# Spartan2Bone.net
KiCad netlist of a schematic drawn in EAGLE
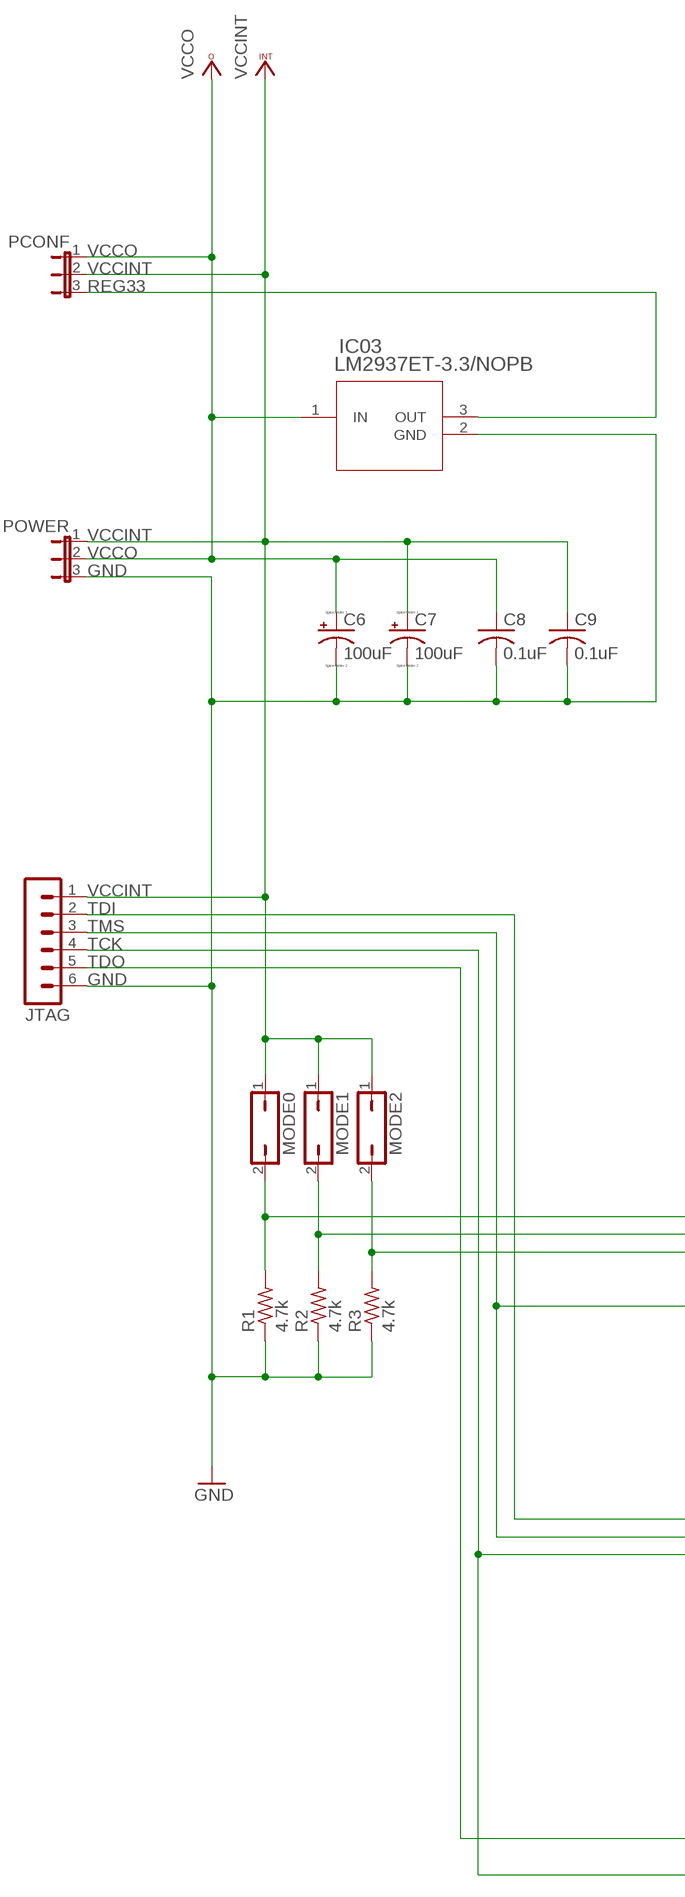
[diagram p0: schematic, sheet 1, part 1 of 2]
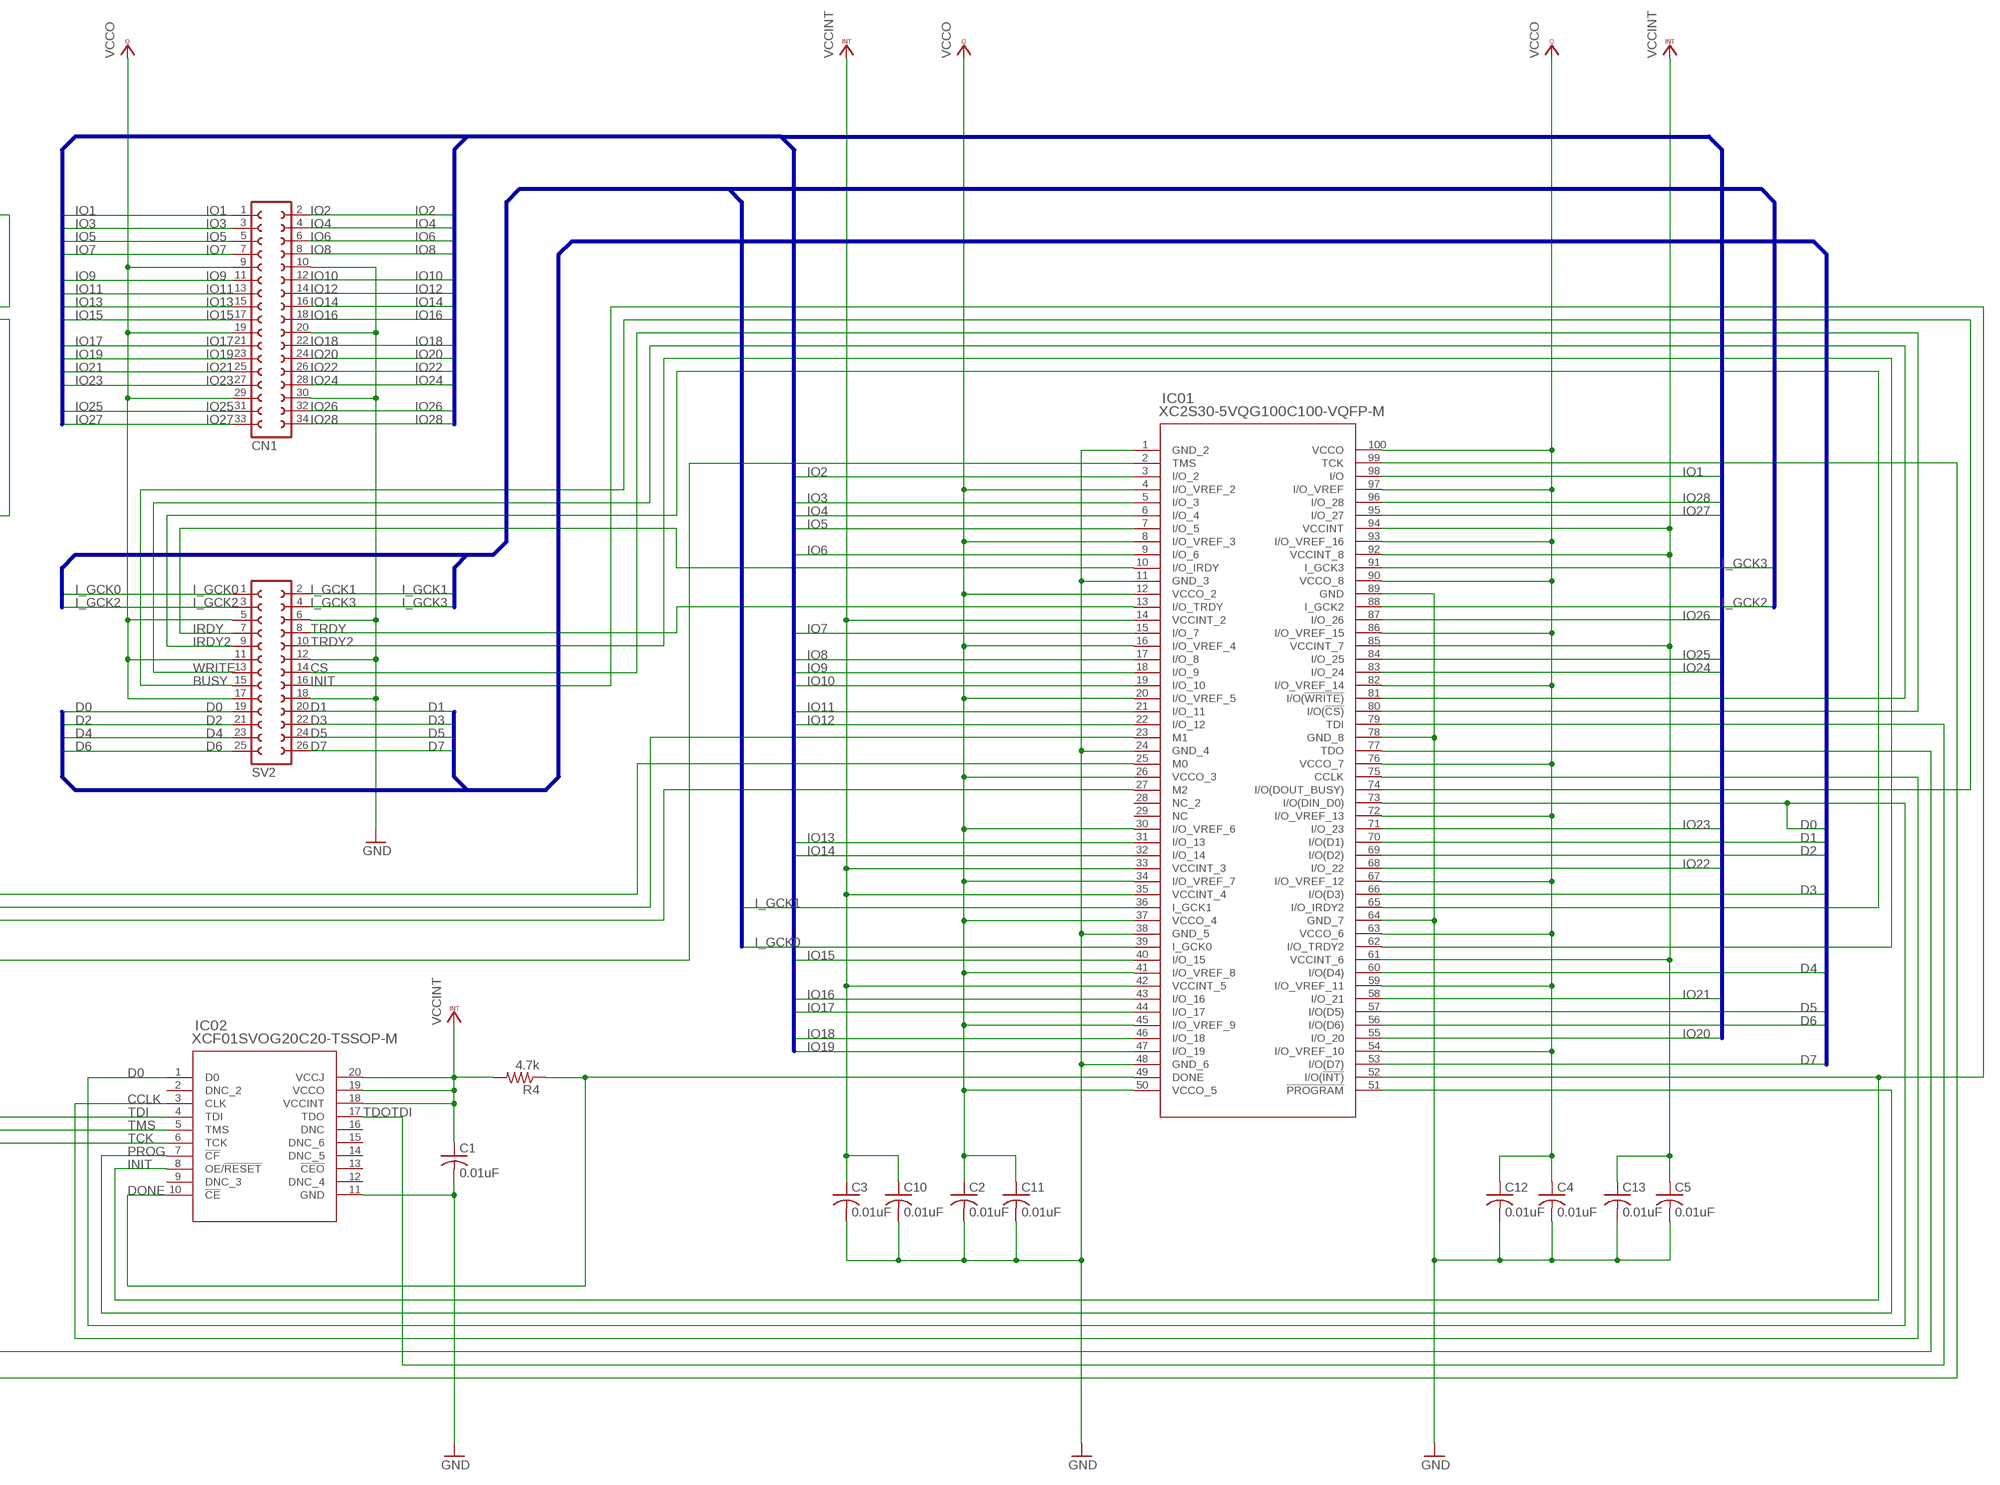
[diagram p1: schematic, sheet 1, part 2 of 2]

(export (version "E")
  (design (tool "Eeschema 10.0.6"))
  (components
    (comp (ref "C1")
      (value "0.01uF")
      (footprint "eagle-import:C050-024X044")
      (libsource (lib "eagle-import") (part "C-US050-024X044"))
    )
    (comp (ref "C2")
      (value "0.01uF")
      (footprint "eagle-import:C050-024X044")
      (libsource (lib "eagle-import") (part "C-US050-024X044"))
    )
    (comp (ref "C3")
      (value "0.01uF")
      (footprint "eagle-import:C050-024X044")
      (libsource (lib "eagle-import") (part "C-US050-024X044"))
    )
    (comp (ref "C4")
      (value "0.01uF")
      (footprint "eagle-import:C050-024X044")
      (libsource (lib "eagle-import") (part "C-US050-024X044"))
    )
    (comp (ref "C5")
      (value "0.01uF")
      (footprint "eagle-import:C050-024X044")
      (libsource (lib "eagle-import") (part "C-US050-024X044"))
    )
    (comp (ref "C6")
      (value "100uF")
      (footprint "eagle-import:E2,5-5")
      (libsource (lib "eagle-import") (part "CPOL-USE2.5-5"))
    )
    (comp (ref "C7")
      (value "100uF")
      (footprint "eagle-import:E2,5-5")
      (libsource (lib "eagle-import") (part "CPOL-USE2.5-5"))
    )
    (comp (ref "C8")
      (value "0.1uF")
      (footprint "eagle-import:C050-024X044")
      (libsource (lib "eagle-import") (part "C-US050-024X044"))
    )
    (comp (ref "C9")
      (value "0.1uF")
      (footprint "eagle-import:C050-024X044")
      (libsource (lib "eagle-import") (part "C-US050-024X044"))
    )
    (comp (ref "C10")
      (value "0.01uF")
      (footprint "eagle-import:C050-024X044")
      (libsource (lib "eagle-import") (part "C-US050-024X044"))
    )
    (comp (ref "C11")
      (value "0.01uF")
      (footprint "eagle-import:C050-024X044")
      (libsource (lib "eagle-import") (part "C-US050-024X044"))
    )
    (comp (ref "C12")
      (value "0.01uF")
      (footprint "eagle-import:C050-024X044")
      (libsource (lib "eagle-import") (part "C-US050-024X044"))
    )
    (comp (ref "C13")
      (value "0.01uF")
      (footprint "eagle-import:C050-024X044")
      (libsource (lib "eagle-import") (part "C-US050-024X044"))
    )
    (comp (ref "CN1")
      (value "FE17-2")
      (footprint "eagle-import:FE17-2")
      (libsource (lib "eagle-import") (part "FE17-2"))
    )
    (comp (ref "IC01")
      (value "XC2S30-5VQG100C100-VQFP-M")
      (footprint "eagle-import:100-VQFP-M")
      (fields (field (name "MANUFACTURER_PART_NUMBER") "XC2S305VQG100C"))
      (libsource (lib "eagle-import") (part "XC2S30-5VQG100C100-VQFP-M"))
    )
    (comp (ref "IC02")
      (value "XCF01SVOG20C20-TSSOP-M")
      (footprint "eagle-import:20-TSSOP-M")
      (fields (field (name "MANUFACTURER_PART_NUMBER") "XCF01SVOG20C"))
      (libsource (lib "eagle-import") (part "XCF01SVOG20C20-TSSOP-M"))
    )
    (comp (ref "IC03")
      (value "LM2937ET-3.3/NOPB")
      (footprint "eagle-import:T03B")
      (fields (field (name "MANUFACTURER_PART_NUMBER") "lm2937et3_3nopb"))
      (libsource (lib "eagle-import") (part "LM2937ET-3.3/NOPB"))
    )
    (comp (ref "JTAG")
      (value "MA06-1")
      (footprint "eagle-import:MA06-1")
      (libsource (lib "eagle-import") (part "MA06-1"))
    )
    (comp (ref "MODE0")
      (value "JP1Q")
      (footprint "eagle-import:JP1")
      (libsource (lib "eagle-import") (part "JP1Q"))
    )
    (comp (ref "MODE1")
      (value "JP1Q")
      (footprint "eagle-import:JP1")
      (libsource (lib "eagle-import") (part "JP1Q"))
    )
    (comp (ref "MODE2")
      (value "JP1Q")
      (footprint "eagle-import:JP1")
      (libsource (lib "eagle-import") (part "JP1Q"))
    )
    (comp (ref "PCONF")
      (value "JP2E")
      (footprint "eagle-import:JP2")
      (libsource (lib "eagle-import") (part "JP2E"))
    )
    (comp (ref "POWER")
      (value "JP2E")
      (footprint "eagle-import:JP2")
      (libsource (lib "eagle-import") (part "JP2E"))
    )
    (comp (ref "R1")
      (value "4.7k")
      (footprint "eagle-import:0204_5")
      (libsource (lib "eagle-import") (part "R-US_0204/5"))
    )
    (comp (ref "R2")
      (value "4.7k")
      (footprint "eagle-import:0204_5")
      (libsource (lib "eagle-import") (part "R-US_0204/5"))
    )
    (comp (ref "R3")
      (value "4.7k")
      (footprint "eagle-import:0204_5")
      (libsource (lib "eagle-import") (part "R-US_0204/5"))
    )
    (comp (ref "R4")
      (value "4.7k")
      (footprint "eagle-import:0204_5")
      (libsource (lib "eagle-import") (part "R-US_0204/5"))
    )
    (comp (ref "SV2")
      (value "FE13-2")
      (footprint "eagle-import:FE13-2")
      (libsource (lib "eagle-import") (part "FE13-2"))
    )
  )
  (nets
    (net (code "1") (name "/BUSY") (class "Default")
      (node (ref "IC01") (pin "74") (pinfunction "I/O(DOUT_BUSY)_74") (pintype "passive"))
      (node (ref "SV2") (pin "15") (pinfunction "15_15") (pintype "passive"))
    )
    (net (code "2") (name "/CCLK") (class "Default")
      (node (ref "IC01") (pin "75") (pinfunction "CCLK_75") (pintype "passive"))
      (node (ref "IC02") (pin "3") (pinfunction "CLK_3") (pintype "passive"))
    )
    (net (code "3") (name "/CS") (class "Default")
      (node (ref "IC01") (pin "80") (pinfunction "I/O(~{CS})_80") (pintype "passive"))
      (node (ref "SV2") (pin "14") (pinfunction "14_14") (pintype "passive"))
    )
    (net (code "4") (name "/D0") (class "Default")
      (node (ref "IC01") (pin "73") (pinfunction "I/O(DIN_D0)_73") (pintype "passive"))
      (node (ref "IC02") (pin "1") (pinfunction "D0_1") (pintype "passive"))
      (node (ref "SV2") (pin "19") (pinfunction "19_19") (pintype "passive"))
    )
    (net (code "5") (name "/D1") (class "Default")
      (node (ref "IC01") (pin "70") (pinfunction "I/O(D1)_70") (pintype "passive"))
      (node (ref "SV2") (pin "20") (pinfunction "20_20") (pintype "passive"))
    )
    (net (code "6") (name "/D2") (class "Default")
      (node (ref "IC01") (pin "69") (pinfunction "I/O(D2)_69") (pintype "passive"))
      (node (ref "SV2") (pin "21") (pinfunction "21_21") (pintype "passive"))
    )
    (net (code "7") (name "/D3") (class "Default")
      (node (ref "IC01") (pin "66") (pinfunction "I/O(D3)_66") (pintype "passive"))
      (node (ref "SV2") (pin "22") (pinfunction "22_22") (pintype "passive"))
    )
    (net (code "8") (name "/D4") (class "Default")
      (node (ref "IC01") (pin "60") (pinfunction "I/O(D4)_60") (pintype "passive"))
      (node (ref "SV2") (pin "23") (pinfunction "23_23") (pintype "passive"))
    )
    (net (code "9") (name "/D5") (class "Default")
      (node (ref "IC01") (pin "57") (pinfunction "I/O(D5)_57") (pintype "passive"))
      (node (ref "SV2") (pin "24") (pinfunction "24_24") (pintype "passive"))
    )
    (net (code "10") (name "/D6") (class "Default")
      (node (ref "IC01") (pin "56") (pinfunction "I/O(D6)_56") (pintype "passive"))
      (node (ref "SV2") (pin "25") (pinfunction "25_25") (pintype "passive"))
    )
    (net (code "11") (name "/D7") (class "Default")
      (node (ref "IC01") (pin "53") (pinfunction "I/O(D7)_53") (pintype "passive"))
      (node (ref "SV2") (pin "26") (pinfunction "26_26") (pintype "passive"))
    )
    (net (code "12") (name "/DONE") (class "Default")
      (node (ref "IC01") (pin "49") (pinfunction "DONE_49") (pintype "passive"))
      (node (ref "IC02") (pin "10") (pinfunction "~{CE}_10") (pintype "passive"))
      (node (ref "R4") (pin "1") (pinfunction "1_1") (pintype "passive"))
    )
    (net (code "13") (name "/INIT") (class "Default")
      (node (ref "IC01") (pin "52") (pinfunction "I/O(~{INT})_52") (pintype "passive"))
      (node (ref "IC02") (pin "8") (pinfunction "OE/~{RESET}_8") (pintype "passive"))
      (node (ref "SV2") (pin "16") (pinfunction "16_16") (pintype "passive"))
    )
    (net (code "14") (name "/IO1") (class "Default")
      (node (ref "CN1") (pin "1") (pinfunction "1_1") (pintype "passive"))
      (node (ref "IC01") (pin "98") (pinfunction "I/O_98") (pintype "passive"))
    )
    (net (code "15") (name "/IO2") (class "Default")
      (node (ref "CN1") (pin "2") (pinfunction "2_2") (pintype "passive"))
      (node (ref "IC01") (pin "3") (pinfunction "I/O_2_3") (pintype "passive"))
    )
    (net (code "16") (name "/IO3") (class "Default")
      (node (ref "CN1") (pin "3") (pinfunction "3_3") (pintype "passive"))
      (node (ref "IC01") (pin "5") (pinfunction "I/O_3_5") (pintype "passive"))
    )
    (net (code "17") (name "/IO4") (class "Default")
      (node (ref "CN1") (pin "4") (pinfunction "4_4") (pintype "passive"))
      (node (ref "IC01") (pin "6") (pinfunction "I/O_4_6") (pintype "passive"))
    )
    (net (code "18") (name "/IO5") (class "Default")
      (node (ref "CN1") (pin "5") (pinfunction "5_5") (pintype "passive"))
      (node (ref "IC01") (pin "7") (pinfunction "I/O_5_7") (pintype "passive"))
    )
    (net (code "19") (name "/IO6") (class "Default")
      (node (ref "CN1") (pin "6") (pinfunction "6_6") (pintype "passive"))
      (node (ref "IC01") (pin "9") (pinfunction "I/O_6_9") (pintype "passive"))
    )
    (net (code "20") (name "/IO7") (class "Default")
      (node (ref "CN1") (pin "7") (pinfunction "7_7") (pintype "passive"))
      (node (ref "IC01") (pin "15") (pinfunction "I/O_7_15") (pintype "passive"))
    )
    (net (code "21") (name "/IO8") (class "Default")
      (node (ref "CN1") (pin "8") (pinfunction "8_8") (pintype "passive"))
      (node (ref "IC01") (pin "17") (pinfunction "I/O_8_17") (pintype "passive"))
    )
    (net (code "22") (name "/IO9") (class "Default")
      (node (ref "CN1") (pin "11") (pinfunction "11_11") (pintype "passive"))
      (node (ref "IC01") (pin "18") (pinfunction "I/O_9_18") (pintype "passive"))
    )
    (net (code "23") (name "/IO10") (class "Default")
      (node (ref "CN1") (pin "12") (pinfunction "12_12") (pintype "passive"))
      (node (ref "IC01") (pin "19") (pinfunction "I/O_10_19") (pintype "passive"))
    )
    (net (code "24") (name "/IO11") (class "Default")
      (node (ref "CN1") (pin "13") (pinfunction "13_13") (pintype "passive"))
      (node (ref "IC01") (pin "21") (pinfunction "I/O_11_21") (pintype "passive"))
    )
    (net (code "25") (name "/IO12") (class "Default")
      (node (ref "CN1") (pin "14") (pinfunction "14_14") (pintype "passive"))
      (node (ref "IC01") (pin "22") (pinfunction "I/O_12_22") (pintype "passive"))
    )
    (net (code "26") (name "/IO13") (class "Default")
      (node (ref "CN1") (pin "15") (pinfunction "15_15") (pintype "passive"))
      (node (ref "IC01") (pin "31") (pinfunction "I/O_13_31") (pintype "passive"))
    )
    (net (code "27") (name "/IO14") (class "Default")
      (node (ref "CN1") (pin "16") (pinfunction "16_16") (pintype "passive"))
      (node (ref "IC01") (pin "32") (pinfunction "I/O_14_32") (pintype "passive"))
    )
    (net (code "28") (name "/IO15") (class "Default")
      (node (ref "CN1") (pin "17") (pinfunction "17_17") (pintype "passive"))
      (node (ref "IC01") (pin "40") (pinfunction "I/O_15_40") (pintype "passive"))
    )
    (net (code "29") (name "/IO16") (class "Default")
      (node (ref "CN1") (pin "18") (pinfunction "18_18") (pintype "passive"))
      (node (ref "IC01") (pin "43") (pinfunction "I/O_16_43") (pintype "passive"))
    )
    (net (code "30") (name "/IO17") (class "Default")
      (node (ref "CN1") (pin "21") (pinfunction "21_21") (pintype "passive"))
      (node (ref "IC01") (pin "44") (pinfunction "I/O_17_44") (pintype "passive"))
    )
    (net (code "31") (name "/IO18") (class "Default")
      (node (ref "CN1") (pin "22") (pinfunction "22_22") (pintype "passive"))
      (node (ref "IC01") (pin "46") (pinfunction "I/O_18_46") (pintype "passive"))
    )
    (net (code "32") (name "/IO19") (class "Default")
      (node (ref "CN1") (pin "23") (pinfunction "23_23") (pintype "passive"))
      (node (ref "IC01") (pin "47") (pinfunction "I/O_19_47") (pintype "passive"))
    )
    (net (code "33") (name "/IO20") (class "Default")
      (node (ref "CN1") (pin "24") (pinfunction "24_24") (pintype "passive"))
      (node (ref "IC01") (pin "55") (pinfunction "I/O_20_55") (pintype "passive"))
    )
    (net (code "34") (name "/IO21") (class "Default")
      (node (ref "CN1") (pin "25") (pinfunction "25_25") (pintype "passive"))
      (node (ref "IC01") (pin "58") (pinfunction "I/O_21_58") (pintype "passive"))
    )
    (net (code "35") (name "/IO22") (class "Default")
      (node (ref "CN1") (pin "26") (pinfunction "26_26") (pintype "passive"))
      (node (ref "IC01") (pin "68") (pinfunction "I/O_22_68") (pintype "passive"))
    )
    (net (code "36") (name "/IO23") (class "Default")
      (node (ref "CN1") (pin "27") (pinfunction "27_27") (pintype "passive"))
      (node (ref "IC01") (pin "71") (pinfunction "I/O_23_71") (pintype "passive"))
    )
    (net (code "37") (name "/IO24") (class "Default")
      (node (ref "CN1") (pin "28") (pinfunction "28_28") (pintype "passive"))
      (node (ref "IC01") (pin "83") (pinfunction "I/O_24_83") (pintype "passive"))
    )
    (net (code "38") (name "/IO25") (class "Default")
      (node (ref "CN1") (pin "31") (pinfunction "31_31") (pintype "passive"))
      (node (ref "IC01") (pin "84") (pinfunction "I/O_25_84") (pintype "passive"))
    )
    (net (code "39") (name "/IO26") (class "Default")
      (node (ref "CN1") (pin "32") (pinfunction "32_32") (pintype "passive"))
      (node (ref "IC01") (pin "87") (pinfunction "I/O_26_87") (pintype "passive"))
    )
    (net (code "40") (name "/IO27") (class "Default")
      (node (ref "CN1") (pin "33") (pinfunction "33_33") (pintype "passive"))
      (node (ref "IC01") (pin "95") (pinfunction "I/O_27_95") (pintype "passive"))
    )
    (net (code "41") (name "/IO28") (class "Default")
      (node (ref "CN1") (pin "34") (pinfunction "34_34") (pintype "passive"))
      (node (ref "IC01") (pin "96") (pinfunction "I/O_28_96") (pintype "passive"))
    )
    (net (code "42") (name "/IRDY") (class "Default")
      (node (ref "IC01") (pin "10") (pinfunction "I/O_IRDY_10") (pintype "passive"))
      (node (ref "SV2") (pin "7") (pinfunction "7_7") (pintype "passive"))
    )
    (net (code "43") (name "/IRDY2") (class "Default")
      (node (ref "IC01") (pin "65") (pinfunction "I/O_IRDY2_65") (pintype "passive"))
      (node (ref "SV2") (pin "9") (pinfunction "9_9") (pintype "passive"))
    )
    (net (code "44") (name "/I_GCK0") (class "Default")
      (node (ref "IC01") (pin "39") (pinfunction "I_GCK0_39") (pintype "passive"))
      (node (ref "SV2") (pin "1") (pinfunction "1_1") (pintype "passive"))
    )
    (net (code "45") (name "/I_GCK1") (class "Default")
      (node (ref "IC01") (pin "36") (pinfunction "I_GCK1_36") (pintype "passive"))
      (node (ref "SV2") (pin "2") (pinfunction "2_2") (pintype "passive"))
    )
    (net (code "46") (name "/I_GCK2") (class "Default")
      (node (ref "IC01") (pin "88") (pinfunction "I_GCK2_88") (pintype "passive"))
      (node (ref "SV2") (pin "3") (pinfunction "3_3") (pintype "passive"))
    )
    (net (code "47") (name "/I_GCK3") (class "Default")
      (node (ref "IC01") (pin "91") (pinfunction "I_GCK3_91") (pintype "passive"))
      (node (ref "SV2") (pin "4") (pinfunction "4_4") (pintype "passive"))
    )
    (net (code "48") (name "/PROG") (class "Default")
      (node (ref "IC01") (pin "51") (pinfunction "~{PROGRAM}_51") (pintype "passive"))
      (node (ref "IC02") (pin "7") (pinfunction "~{CF}_7") (pintype "passive"))
    )
    (net (code "49") (name "/REG33") (class "Default")
      (node (ref "IC03") (pin "3") (pinfunction "OUT_3") (pintype "power_in"))
      (node (ref "PCONF") (pin "3") (pinfunction "3_3") (pintype "passive"))
    )
    (net (code "50") (name "/TCK") (class "Default")
      (node (ref "IC01") (pin "99") (pinfunction "TCK_99") (pintype "passive"))
      (node (ref "IC02") (pin "6") (pinfunction "TCK_6") (pintype "passive"))
      (node (ref "JTAG") (pin "4") (pinfunction "4_4") (pintype "passive"))
    )
    (net (code "51") (name "/TDI") (class "Default")
      (node (ref "IC02") (pin "4") (pinfunction "TDI_4") (pintype "passive"))
      (node (ref "JTAG") (pin "2") (pinfunction "2_2") (pintype "passive"))
    )
    (net (code "52") (name "/TDO") (class "Default")
      (node (ref "IC01") (pin "77") (pinfunction "TDO_77") (pintype "passive"))
      (node (ref "JTAG") (pin "5") (pinfunction "5_5") (pintype "passive"))
    )
    (net (code "53") (name "/TDOTDI") (class "Default")
      (node (ref "IC01") (pin "79") (pinfunction "TDI_79") (pintype "passive"))
      (node (ref "IC02") (pin "17") (pinfunction "TDO_17") (pintype "passive"))
    )
    (net (code "54") (name "/TMS") (class "Default")
      (node (ref "IC01") (pin "2") (pinfunction "TMS_2") (pintype "passive"))
      (node (ref "IC02") (pin "5") (pinfunction "TMS_5") (pintype "passive"))
      (node (ref "JTAG") (pin "3") (pinfunction "3_3") (pintype "passive"))
    )
    (net (code "55") (name "/TRDY") (class "Default")
      (node (ref "IC01") (pin "13") (pinfunction "I/O_TRDY_13") (pintype "passive"))
      (node (ref "SV2") (pin "8") (pinfunction "8_8") (pintype "passive"))
    )
    (net (code "56") (name "/TRDY2") (class "Default")
      (node (ref "IC01") (pin "62") (pinfunction "I/O_TRDY2_62") (pintype "passive"))
      (node (ref "SV2") (pin "10") (pinfunction "10_10") (pintype "passive"))
    )
    (net (code "57") (name "/WRITE") (class "Default")
      (node (ref "IC01") (pin "81") (pinfunction "I/O(~{WRITE})_81") (pintype "passive"))
      (node (ref "SV2") (pin "13") (pinfunction "13_13") (pintype "passive"))
    )
    (net (code "58") (name "GND") (class "Default")
      (node (ref "C1") (pin "2") (pinfunction "2_2") (pintype "passive"))
      (node (ref "C10") (pin "2") (pinfunction "2_2") (pintype "passive"))
      (node (ref "C11") (pin "2") (pinfunction "2_2") (pintype "passive"))
      (node (ref "C12") (pin "2") (pinfunction "2_2") (pintype "passive"))
      (node (ref "C13") (pin "2") (pinfunction "2_2") (pintype "passive"))
      (node (ref "C2") (pin "2") (pinfunction "2_2") (pintype "passive"))
      (node (ref "C3") (pin "2") (pinfunction "2_2") (pintype "passive"))
      (node (ref "C4") (pin "2") (pinfunction "2_2") (pintype "passive"))
      (node (ref "C5") (pin "2") (pinfunction "2_2") (pintype "passive"))
      (node (ref "C6") (pin "-") (pinfunction "-_-") (pintype "passive"))
      (node (ref "C7") (pin "-") (pinfunction "-_-") (pintype "passive"))
      (node (ref "C8") (pin "2") (pinfunction "2_2") (pintype "passive"))
      (node (ref "C9") (pin "2") (pinfunction "2_2") (pintype "passive"))
      (node (ref "CN1") (pin "10") (pinfunction "10_10") (pintype "passive"))
      (node (ref "CN1") (pin "20") (pinfunction "20_20") (pintype "passive"))
      (node (ref "CN1") (pin "30") (pinfunction "30_30") (pintype "passive"))
      (node (ref "IC01") (pin "1") (pinfunction "GND_2_1") (pintype "passive"))
      (node (ref "IC01") (pin "11") (pinfunction "GND_3_11") (pintype "passive"))
      (node (ref "IC01") (pin "24") (pinfunction "GND_4_24") (pintype "passive"))
      (node (ref "IC01") (pin "38") (pinfunction "GND_5_38") (pintype "passive"))
      (node (ref "IC01") (pin "48") (pinfunction "GND_6_48") (pintype "passive"))
      (node (ref "IC01") (pin "64") (pinfunction "GND_7_64") (pintype "passive"))
      (node (ref "IC01") (pin "78") (pinfunction "GND_8_78") (pintype "passive"))
      (node (ref "IC01") (pin "89") (pinfunction "GND_89") (pintype "passive"))
      (node (ref "IC02") (pin "11") (pinfunction "GND_11") (pintype "passive"))
      (node (ref "IC03") (pin "2") (pinfunction "GND_2") (pintype "power_in"))
      (node (ref "JTAG") (pin "6") (pinfunction "6_6") (pintype "passive"))
      (node (ref "POWER") (pin "3") (pinfunction "3_3") (pintype "passive"))
      (node (ref "R1") (pin "1") (pinfunction "1_1") (pintype "passive"))
      (node (ref "R2") (pin "1") (pinfunction "1_1") (pintype "passive"))
      (node (ref "R3") (pin "1") (pinfunction "1_1") (pintype "passive"))
      (node (ref "SV2") (pin "12") (pinfunction "12_12") (pintype "passive"))
      (node (ref "SV2") (pin "18") (pinfunction "18_18") (pintype "passive"))
      (node (ref "SV2") (pin "6") (pinfunction "6_6") (pintype "passive"))
    )
    (net (code "59") (name "Net-(IC01-M0)") (class "Default")
      (node (ref "IC01") (pin "25") (pinfunction "M0_25") (pintype "passive"))
      (node (ref "MODE0") (pin "2") (pinfunction "2_2") (pintype "passive"))
      (node (ref "R1") (pin "2") (pinfunction "2_2") (pintype "passive"))
    )
    (net (code "60") (name "Net-(IC01-M1)") (class "Default")
      (node (ref "IC01") (pin "23") (pinfunction "M1_23") (pintype "passive"))
      (node (ref "MODE1") (pin "2") (pinfunction "2_2") (pintype "passive"))
      (node (ref "R2") (pin "2") (pinfunction "2_2") (pintype "passive"))
    )
    (net (code "61") (name "Net-(IC01-M2)") (class "Default")
      (node (ref "IC01") (pin "27") (pinfunction "M2_27") (pintype "passive"))
      (node (ref "MODE2") (pin "2") (pinfunction "2_2") (pintype "passive"))
      (node (ref "R3") (pin "2") (pinfunction "2_2") (pintype "passive"))
    )
    (net (code "62") (name "VCCINT") (class "Default")
      (node (ref "C1") (pin "1") (pinfunction "1_1") (pintype "passive"))
      (node (ref "C10") (pin "1") (pinfunction "1_1") (pintype "passive"))
      (node (ref "C13") (pin "1") (pinfunction "1_1") (pintype "passive"))
      (node (ref "C3") (pin "1") (pinfunction "1_1") (pintype "passive"))
      (node (ref "C5") (pin "1") (pinfunction "1_1") (pintype "passive"))
      (node (ref "C7") (pin "+") (pinfunction "+_+") (pintype "passive"))
      (node (ref "C9") (pin "1") (pinfunction "1_1") (pintype "passive"))
      (node (ref "IC01") (pin "14") (pinfunction "VCCINT_2_14") (pintype "passive"))
      (node (ref "IC01") (pin "33") (pinfunction "VCCINT_3_33") (pintype "passive"))
      (node (ref "IC01") (pin "35") (pinfunction "VCCINT_4_35") (pintype "passive"))
      (node (ref "IC01") (pin "42") (pinfunction "VCCINT_5_42") (pintype "passive"))
      (node (ref "IC01") (pin "61") (pinfunction "VCCINT_6_61") (pintype "passive"))
      (node (ref "IC01") (pin "85") (pinfunction "VCCINT_7_85") (pintype "passive"))
      (node (ref "IC01") (pin "92") (pinfunction "VCCINT_8_92") (pintype "passive"))
      (node (ref "IC01") (pin "94") (pinfunction "VCCINT_94") (pintype "passive"))
      (node (ref "IC02") (pin "18") (pinfunction "VCCINT_18") (pintype "passive"))
      (node (ref "IC02") (pin "19") (pinfunction "VCCO_19") (pintype "passive"))
      (node (ref "IC02") (pin "20") (pinfunction "VCCJ_20") (pintype "passive"))
      (node (ref "JTAG") (pin "1") (pinfunction "1_1") (pintype "passive"))
      (node (ref "MODE0") (pin "1") (pinfunction "1_1") (pintype "passive"))
      (node (ref "MODE1") (pin "1") (pinfunction "1_1") (pintype "passive"))
      (node (ref "MODE2") (pin "1") (pinfunction "1_1") (pintype "passive"))
      (node (ref "PCONF") (pin "2") (pinfunction "2_2") (pintype "passive"))
      (node (ref "POWER") (pin "1") (pinfunction "1_1") (pintype "passive"))
      (node (ref "R4") (pin "2") (pinfunction "2_2") (pintype "passive"))
    )
    (net (code "63") (name "VCCO") (class "Default")
      (node (ref "C11") (pin "1") (pinfunction "1_1") (pintype "passive"))
      (node (ref "C12") (pin "1") (pinfunction "1_1") (pintype "passive"))
      (node (ref "C2") (pin "1") (pinfunction "1_1") (pintype "passive"))
      (node (ref "C4") (pin "1") (pinfunction "1_1") (pintype "passive"))
      (node (ref "C6") (pin "+") (pinfunction "+_+") (pintype "passive"))
      (node (ref "C8") (pin "1") (pinfunction "1_1") (pintype "passive"))
      (node (ref "CN1") (pin "19") (pinfunction "19_19") (pintype "passive"))
      (node (ref "CN1") (pin "29") (pinfunction "29_29") (pintype "passive"))
      (node (ref "CN1") (pin "9") (pinfunction "9_9") (pintype "passive"))
      (node (ref "IC01") (pin "100") (pinfunction "VCCO_100") (pintype "passive"))
      (node (ref "IC01") (pin "12") (pinfunction "VCCO_2_12") (pintype "passive"))
      (node (ref "IC01") (pin "16") (pinfunction "I/O_VREF_4_16") (pintype "passive"))
      (node (ref "IC01") (pin "20") (pinfunction "I/O_VREF_5_20") (pintype "passive"))
      (node (ref "IC01") (pin "26") (pinfunction "VCCO_3_26") (pintype "passive"))
      (node (ref "IC01") (pin "30") (pinfunction "I/O_VREF_6_30") (pintype "passive"))
      (node (ref "IC01") (pin "34") (pinfunction "I/O_VREF_7_34") (pintype "passive"))
      (node (ref "IC01") (pin "37") (pinfunction "VCCO_4_37") (pintype "passive"))
      (node (ref "IC01") (pin "4") (pinfunction "I/O_VREF_2_4") (pintype "passive"))
      (node (ref "IC01") (pin "41") (pinfunction "I/O_VREF_8_41") (pintype "passive"))
      (node (ref "IC01") (pin "45") (pinfunction "I/O_VREF_9_45") (pintype "passive"))
      (node (ref "IC01") (pin "50") (pinfunction "VCCO_5_50") (pintype "passive"))
      (node (ref "IC01") (pin "54") (pinfunction "I/O_VREF_10_54") (pintype "passive"))
      (node (ref "IC01") (pin "59") (pinfunction "I/O_VREF_11_59") (pintype "passive"))
      (node (ref "IC01") (pin "63") (pinfunction "VCCO_6_63") (pintype "passive"))
      (node (ref "IC01") (pin "67") (pinfunction "I/O_VREF_12_67") (pintype "passive"))
      (node (ref "IC01") (pin "72") (pinfunction "I/O_VREF_13_72") (pintype "passive"))
      (node (ref "IC01") (pin "76") (pinfunction "VCCO_7_76") (pintype "passive"))
      (node (ref "IC01") (pin "8") (pinfunction "I/O_VREF_3_8") (pintype "passive"))
      (node (ref "IC01") (pin "82") (pinfunction "I/O_VREF_14_82") (pintype "passive"))
      (node (ref "IC01") (pin "86") (pinfunction "I/O_VREF_15_86") (pintype "passive"))
      (node (ref "IC01") (pin "90") (pinfunction "VCCO_8_90") (pintype "passive"))
      (node (ref "IC01") (pin "93") (pinfunction "I/O_VREF_16_93") (pintype "passive"))
      (node (ref "IC01") (pin "97") (pinfunction "I/O_VREF_97") (pintype "passive"))
      (node (ref "IC03") (pin "1") (pinfunction "IN_1") (pintype "power_in"))
      (node (ref "PCONF") (pin "1") (pinfunction "1_1") (pintype "passive"))
      (node (ref "POWER") (pin "2") (pinfunction "2_2") (pintype "passive"))
      (node (ref "SV2") (pin "11") (pinfunction "11_11") (pintype "passive"))
      (node (ref "SV2") (pin "17") (pinfunction "17_17") (pintype "passive"))
      (node (ref "SV2") (pin "5") (pinfunction "5_5") (pintype "passive"))
    )
    (net (code "64") (name "unconnected-(IC01-NC-Pad29)") (class "Default")
      (node (ref "IC01") (pin "29") (pinfunction "NC_29") (pintype "passive"))
    )
    (net (code "65") (name "unconnected-(IC01-NC_2-Pad28)") (class "Default")
      (node (ref "IC01") (pin "28") (pinfunction "NC_2_28") (pintype "passive"))
    )
    (net (code "66") (name "unconnected-(IC02-DNC-Pad16)") (class "Default")
      (node (ref "IC02") (pin "16") (pinfunction "DNC_16") (pintype "passive"))
    )
    (net (code "67") (name "unconnected-(IC02-DNC_2-Pad2)") (class "Default")
      (node (ref "IC02") (pin "2") (pinfunction "DNC_2_2") (pintype "passive"))
    )
    (net (code "68") (name "unconnected-(IC02-DNC_3-Pad9)") (class "Default")
      (node (ref "IC02") (pin "9") (pinfunction "DNC_3_9") (pintype "passive"))
    )
    (net (code "69") (name "unconnected-(IC02-DNC_4-Pad12)") (class "Default")
      (node (ref "IC02") (pin "12") (pinfunction "DNC_4_12") (pintype "passive"))
    )
    (net (code "70") (name "unconnected-(IC02-DNC_5-Pad14)") (class "Default")
      (node (ref "IC02") (pin "14") (pinfunction "DNC_5_14") (pintype "passive"))
    )
    (net (code "71") (name "unconnected-(IC02-DNC_6-Pad15)") (class "Default")
      (node (ref "IC02") (pin "15") (pinfunction "DNC_6_15") (pintype "passive"))
    )
    (net (code "72") (name "unconnected-(IC02-~{CEO}-Pad13)") (class "Default")
      (node (ref "IC02") (pin "13") (pinfunction "~{CEO}_13") (pintype "passive"))
    )
  )
)
